# CortexM0_development_board.net
KiCad netlist of a schematic drawn in EAGLE
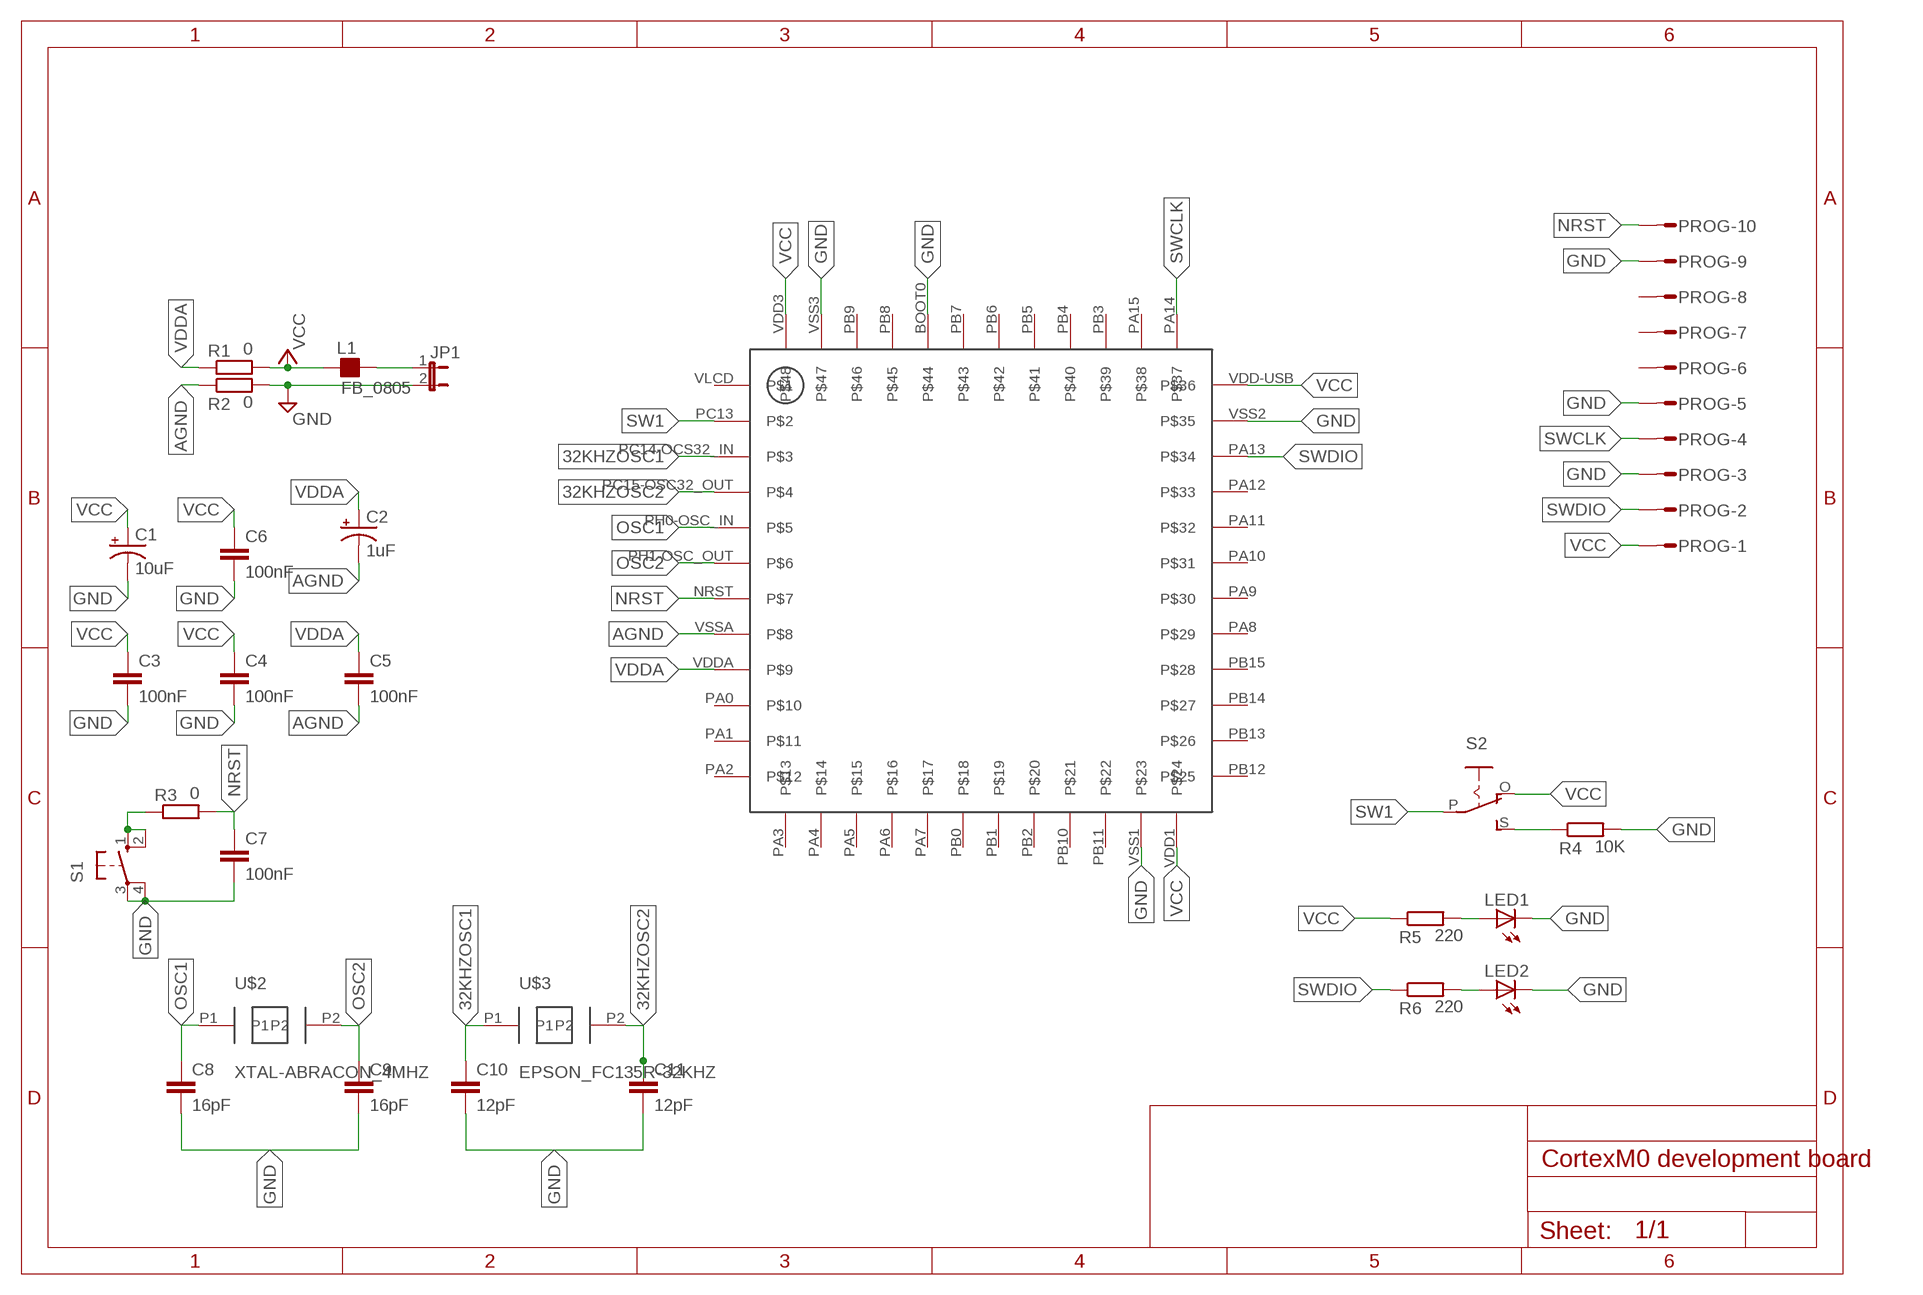
[diagram p0: schematic, sheet 1]

(export (version "E")
  (design (tool "Eeschema 10.0.6"))
  (components
    (comp (ref "C1")
      (value "10uF")
      (footprint "eagle-import:CAPMP3216X180N")
      (libsource (lib "eagle-import") (part "C-POL-USTANTALUM-1206(3216-METRIC)_"))
    )
    (comp (ref "C2")
      (value "1uF")
      (footprint "eagle-import:CAPMP3216X180N")
      (libsource (lib "eagle-import") (part "C-POL-USTANTALUM-1206(3216-METRIC)_"))
    )
    (comp (ref "C3")
      (value "100nF")
      (footprint "eagle-import:C0805")
      (libsource (lib "eagle-import") (part "C-EUC0805"))
    )
    (comp (ref "C4")
      (value "100nF")
      (footprint "eagle-import:C0805")
      (libsource (lib "eagle-import") (part "C-EUC0805"))
    )
    (comp (ref "C5")
      (value "100nF")
      (footprint "eagle-import:C0805")
      (libsource (lib "eagle-import") (part "C-EUC0805"))
    )
    (comp (ref "C6")
      (value "100nF")
      (footprint "eagle-import:C0805")
      (libsource (lib "eagle-import") (part "C-EUC0805"))
    )
    (comp (ref "C7")
      (value "100nF")
      (footprint "eagle-import:C0805")
      (libsource (lib "eagle-import") (part "C-EUC0805"))
    )
    (comp (ref "C8")
      (value "16pF")
      (footprint "eagle-import:C0805")
      (libsource (lib "eagle-import") (part "C-EUC0805"))
    )
    (comp (ref "C9")
      (value "16pF")
      (footprint "eagle-import:C0805")
      (libsource (lib "eagle-import") (part "C-EUC0805"))
    )
    (comp (ref "C10")
      (value "12pF")
      (footprint "eagle-import:C0805")
      (libsource (lib "eagle-import") (part "C-EUC0805"))
    )
    (comp (ref "C11")
      (value "12pF")
      (footprint "eagle-import:C0805")
      (libsource (lib "eagle-import") (part "C-EUC0805"))
    )
    (comp (ref "JP1")
      (value "JP1E")
      (footprint "eagle-import:JP1")
      (libsource (lib "eagle-import") (part "JP1E"))
    )
    (comp (ref "L1")
      (value "FB_0805")
      (footprint "eagle-import:L0805")
      (libsource (lib "eagle-import") (part "FB_0805"))
    )
    (comp (ref "LED1")
      (value "LED")
      (footprint "eagle-import:SMARTLED-TTW")
      (libsource (lib "eagle-import") (part "LED"))
    )
    (comp (ref "LED2")
      (value "LED")
      (footprint "eagle-import:SMARTLED-TTW")
      (libsource (lib "eagle-import") (part "LED"))
    )
    (comp (ref "PROG")
      (value "S10P")
      (footprint "eagle-import:S10P")
      (libsource (lib "eagle-import") (part "S10P"))
    )
    (comp (ref "R1")
      (value "0")
      (footprint "eagle-import:R0805")
      (libsource (lib "eagle-import") (part "R-EU_R0805"))
    )
    (comp (ref "R2")
      (value "0")
      (footprint "eagle-import:R0805")
      (libsource (lib "eagle-import") (part "R-EU_R0805"))
    )
    (comp (ref "R3")
      (value "0")
      (footprint "eagle-import:R0805")
      (libsource (lib "eagle-import") (part "R-EU_R0805"))
    )
    (comp (ref "R4")
      (value "10K")
      (footprint "eagle-import:R0805")
      (libsource (lib "eagle-import") (part "R-EU_R0805"))
    )
    (comp (ref "R5")
      (value "220")
      (footprint "eagle-import:R0805")
      (libsource (lib "eagle-import") (part "R-EU_R0805"))
    )
    (comp (ref "R6")
      (value "220")
      (footprint "eagle-import:R0805")
      (libsource (lib "eagle-import") (part "R-EU_R0805"))
    )
    (comp (ref "S1")
      (value "10-XX")
      (footprint "eagle-import:B3F-10XX")
      (fields (field (name "MPN") "B3F-1000"))
      (libsource (lib "eagle-import") (part "10-XX"))
    )
    (comp (ref "S2")
      (value "EG1218S")
      (footprint "eagle-import:EG1218")
      (libsource (lib "eagle-import") (part "EG1218S"))
    )
    (comp (ref "U$1")
      (value "LQFP_48")
      (footprint "eagle-import:STM32L083CZ")
      (libsource (lib "eagle-import") (part "LQFP_48"))
    )
    (comp (ref "U$2")
      (value "XTAL-ABRACON_4MHZ")
      (footprint "eagle-import:XTAL_ABRACON_4MHZ")
      (libsource (lib "eagle-import") (part "XTAL-ABRACON_4MHZ"))
    )
    (comp (ref "U$3")
      (value "EPSON_FC135R-32KHZ")
      (footprint "eagle-import:EPSON_FC135R_32KHZ")
      (libsource (lib "eagle-import") (part "EPSON_FC135R-32KHZ"))
    )
  )
  (nets
    (net (code "1") (name "32KHZOSC1") (class "Default")
      (node (ref "C10") (pin "1") (pinfunction "1_1") (pintype "passive"))
      (node (ref "U$1") (pin "PC14-OCS32_IN") (pinfunction "P$3_PC14-OCS32_IN") (pintype "bidirectional"))
      (node (ref "U$3") (pin "P1") (pinfunction "P1_P1") (pintype "bidirectional"))
    )
    (net (code "2") (name "32KHZOSC2") (class "Default")
      (node (ref "C11") (pin "1") (pinfunction "1_1") (pintype "passive"))
      (node (ref "U$1") (pin "PC15-OSC32_OUT") (pinfunction "P$4_PC15-OSC32_OUT") (pintype "bidirectional"))
      (node (ref "U$3") (pin "P2") (pinfunction "P2_P2") (pintype "bidirectional"))
    )
    (net (code "3") (name "AGND") (class "Default")
      (node (ref "C2") (pin "2") (pinfunction "-_2") (pintype "passive"))
      (node (ref "C5") (pin "2") (pinfunction "2_2") (pintype "passive"))
      (node (ref "R2") (pin "1") (pinfunction "1_1") (pintype "passive"))
      (node (ref "U$1") (pin "VSSA") (pinfunction "P$8_VSSA") (pintype "bidirectional"))
    )
    (net (code "4") (name "GND") (class "Default")
      (node (ref "C1") (pin "2") (pinfunction "-_2") (pintype "passive"))
      (node (ref "C10") (pin "2") (pinfunction "2_2") (pintype "passive"))
      (node (ref "C11") (pin "2") (pinfunction "2_2") (pintype "passive"))
      (node (ref "C3") (pin "2") (pinfunction "2_2") (pintype "passive"))
      (node (ref "C4") (pin "2") (pinfunction "2_2") (pintype "passive"))
      (node (ref "C6") (pin "2") (pinfunction "2_2") (pintype "passive"))
      (node (ref "C7") (pin "2") (pinfunction "2_2") (pintype "passive"))
      (node (ref "C8") (pin "2") (pinfunction "2_2") (pintype "passive"))
      (node (ref "C9") (pin "2") (pinfunction "2_2") (pintype "passive"))
      (node (ref "JP1") (pin "2") (pinfunction "2_2") (pintype "passive"))
      (node (ref "LED1") (pin "C@1") (pinfunction "C_C@1") (pintype "passive"))
      (node (ref "LED2") (pin "C@1") (pinfunction "C_C@1") (pintype "passive"))
      (node (ref "PROG") (pin "3") (pinfunction "S_3") (pintype "passive"))
      (node (ref "PROG") (pin "5") (pinfunction "S_5") (pintype "passive"))
      (node (ref "PROG") (pin "9") (pinfunction "S_9") (pintype "passive"))
      (node (ref "R2") (pin "2") (pinfunction "2_2") (pintype "passive"))
      (node (ref "R4") (pin "2") (pinfunction "2_2") (pintype "passive"))
      (node (ref "S1") (pin "3") (pinfunction "P_3") (pintype "passive"))
      (node (ref "S1") (pin "4") (pinfunction "P1_4") (pintype "passive"))
      (node (ref "U$1") (pin "BOOT0") (pinfunction "P$44_BOOT0") (pintype "bidirectional"))
      (node (ref "U$1") (pin "VSS1") (pinfunction "P$23_VSS1") (pintype "bidirectional"))
      (node (ref "U$1") (pin "VSS2") (pinfunction "P$35_VSS2") (pintype "bidirectional"))
      (node (ref "U$1") (pin "VSS3") (pinfunction "P$47_VSS3") (pintype "bidirectional"))
    )
    (net (code "5") (name "NRST") (class "Default")
      (node (ref "C7") (pin "1") (pinfunction "1_1") (pintype "passive"))
      (node (ref "PROG") (pin "10") (pinfunction "S_10") (pintype "passive"))
      (node (ref "R3") (pin "2") (pinfunction "2_2") (pintype "passive"))
      (node (ref "U$1") (pin "NRST") (pinfunction "P$7_NRST") (pintype "bidirectional"))
    )
    (net (code "6") (name "Net-(JP1-Pad1)") (class "Default")
      (node (ref "JP1") (pin "1") (pinfunction "1_1") (pintype "passive"))
      (node (ref "L1") (pin "2") (pinfunction "2_2") (pintype "passive"))
    )
    (net (code "7") (name "Net-(LED1-A)") (class "Default")
      (node (ref "LED1") (pin "A@1") (pinfunction "A_A@1") (pintype "passive"))
      (node (ref "R5") (pin "2") (pinfunction "2_2") (pintype "passive"))
    )
    (net (code "8") (name "Net-(LED2-A)") (class "Default")
      (node (ref "LED2") (pin "A@1") (pinfunction "A_A@1") (pintype "passive"))
      (node (ref "R6") (pin "2") (pinfunction "2_2") (pintype "passive"))
    )
    (net (code "9") (name "Net-(R4-Pad1)") (class "Default")
      (node (ref "R4") (pin "1") (pinfunction "1_1") (pintype "passive"))
      (node (ref "S2") (pin "S") (pinfunction "S_S") (pintype "passive"))
    )
    (net (code "10") (name "Net-(S1-S)") (class "Default")
      (node (ref "R3") (pin "1") (pinfunction "1_1") (pintype "passive"))
      (node (ref "S1") (pin "1") (pinfunction "S_1") (pintype "passive"))
      (node (ref "S1") (pin "2") (pinfunction "S1_2") (pintype "passive"))
    )
    (net (code "11") (name "OSC1") (class "Default")
      (node (ref "C8") (pin "1") (pinfunction "1_1") (pintype "passive"))
      (node (ref "U$1") (pin "PH0-OSC_IN") (pinfunction "P$5_PH0-OSC_IN") (pintype "bidirectional"))
      (node (ref "U$2") (pin "P1") (pinfunction "P1_P1") (pintype "bidirectional"))
    )
    (net (code "12") (name "OSC2") (class "Default")
      (node (ref "C9") (pin "1") (pinfunction "1_1") (pintype "passive"))
      (node (ref "U$1") (pin "PH1-OSC_OUT") (pinfunction "P$6_PH1-OSC_OUT") (pintype "bidirectional"))
      (node (ref "U$2") (pin "P2") (pinfunction "P2_P2") (pintype "bidirectional"))
    )
    (net (code "13") (name "SW1") (class "Default")
      (node (ref "S2") (pin "P") (pinfunction "P_P") (pintype "passive"))
      (node (ref "U$1") (pin "PC13") (pinfunction "P$2_PC13") (pintype "bidirectional"))
    )
    (net (code "14") (name "SWCLK") (class "Default")
      (node (ref "PROG") (pin "4") (pinfunction "S_4") (pintype "passive"))
      (node (ref "U$1") (pin "PA14") (pinfunction "P$37_PA14") (pintype "bidirectional"))
    )
    (net (code "15") (name "SWDIO") (class "Default")
      (node (ref "PROG") (pin "2") (pinfunction "S_2") (pintype "passive"))
      (node (ref "R6") (pin "1") (pinfunction "1_1") (pintype "passive"))
      (node (ref "U$1") (pin "PA13") (pinfunction "P$34_PA13") (pintype "bidirectional"))
    )
    (net (code "16") (name "VCC") (class "Default")
      (node (ref "C1") (pin "1") (pinfunction "+_1") (pintype "passive"))
      (node (ref "C3") (pin "1") (pinfunction "1_1") (pintype "passive"))
      (node (ref "C4") (pin "1") (pinfunction "1_1") (pintype "passive"))
      (node (ref "C6") (pin "1") (pinfunction "1_1") (pintype "passive"))
      (node (ref "L1") (pin "1") (pinfunction "1_1") (pintype "passive"))
      (node (ref "PROG") (pin "1") (pinfunction "S_1") (pintype "passive"))
      (node (ref "R1") (pin "2") (pinfunction "2_2") (pintype "passive"))
      (node (ref "R5") (pin "1") (pinfunction "1_1") (pintype "passive"))
      (node (ref "S2") (pin "O") (pinfunction "O_O") (pintype "passive"))
      (node (ref "U$1") (pin "VDD-USB") (pinfunction "P$36_VDD-USB") (pintype "bidirectional"))
      (node (ref "U$1") (pin "VDD1") (pinfunction "P$24_VDD1") (pintype "bidirectional"))
      (node (ref "U$1") (pin "VDD3") (pinfunction "P$48_VDD3") (pintype "bidirectional"))
    )
    (net (code "17") (name "VDDA") (class "Default")
      (node (ref "C2") (pin "1") (pinfunction "+_1") (pintype "passive"))
      (node (ref "C5") (pin "1") (pinfunction "1_1") (pintype "passive"))
      (node (ref "R1") (pin "1") (pinfunction "1_1") (pintype "passive"))
      (node (ref "U$1") (pin "VDDA") (pinfunction "P$9_VDDA") (pintype "bidirectional"))
    )
    (net (code "18") (name "unconnected-(PROGG-S-Pad6)") (class "Default")
      (node (ref "PROG") (pin "6") (pinfunction "S_6") (pintype "passive"))
    )
    (net (code "19") (name "unconnected-(PROGH-S-Pad7)") (class "Default")
      (node (ref "PROG") (pin "7") (pinfunction "S_7") (pintype "passive"))
    )
    (net (code "20") (name "unconnected-(PROGI-S-Pad8)") (class "Default")
      (node (ref "PROG") (pin "8") (pinfunction "S_8") (pintype "passive"))
    )
    (net (code "21") (name "unconnected-(U$1-P$1-PadVLCD)") (class "Default")
      (node (ref "U$1") (pin "VLCD") (pinfunction "P$1_VLCD") (pintype "bidirectional"))
    )
    (net (code "22") (name "unconnected-(U$1-P$10-PadPA0)") (class "Default")
      (node (ref "U$1") (pin "PA0") (pinfunction "P$10_PA0") (pintype "bidirectional"))
    )
    (net (code "23") (name "unconnected-(U$1-P$11-PadPA1)") (class "Default")
      (node (ref "U$1") (pin "PA1") (pinfunction "P$11_PA1") (pintype "bidirectional"))
    )
    (net (code "24") (name "unconnected-(U$1-P$12-PadPA2)") (class "Default")
      (node (ref "U$1") (pin "PA2") (pinfunction "P$12_PA2") (pintype "bidirectional"))
    )
    (net (code "25") (name "unconnected-(U$1-P$13-PadPA3)") (class "Default")
      (node (ref "U$1") (pin "PA3") (pinfunction "P$13_PA3") (pintype "bidirectional"))
    )
    (net (code "26") (name "unconnected-(U$1-P$14-PadPA4)") (class "Default")
      (node (ref "U$1") (pin "PA4") (pinfunction "P$14_PA4") (pintype "bidirectional"))
    )
    (net (code "27") (name "unconnected-(U$1-P$15-PadPA5)") (class "Default")
      (node (ref "U$1") (pin "PA5") (pinfunction "P$15_PA5") (pintype "bidirectional"))
    )
    (net (code "28") (name "unconnected-(U$1-P$16-PadPA6)") (class "Default")
      (node (ref "U$1") (pin "PA6") (pinfunction "P$16_PA6") (pintype "bidirectional"))
    )
    (net (code "29") (name "unconnected-(U$1-P$17-PadPA7)") (class "Default")
      (node (ref "U$1") (pin "PA7") (pinfunction "P$17_PA7") (pintype "bidirectional"))
    )
    (net (code "30") (name "unconnected-(U$1-P$18-PadPB0)") (class "Default")
      (node (ref "U$1") (pin "PB0") (pinfunction "P$18_PB0") (pintype "bidirectional"))
    )
    (net (code "31") (name "unconnected-(U$1-P$19-PadPB1)") (class "Default")
      (node (ref "U$1") (pin "PB1") (pinfunction "P$19_PB1") (pintype "bidirectional"))
    )
    (net (code "32") (name "unconnected-(U$1-P$20-PadPB2)") (class "Default")
      (node (ref "U$1") (pin "PB2") (pinfunction "P$20_PB2") (pintype "bidirectional"))
    )
    (net (code "33") (name "unconnected-(U$1-P$21-PadPB10)") (class "Default")
      (node (ref "U$1") (pin "PB10") (pinfunction "P$21_PB10") (pintype "bidirectional"))
    )
    (net (code "34") (name "unconnected-(U$1-P$22-PadPB11)") (class "Default")
      (node (ref "U$1") (pin "PB11") (pinfunction "P$22_PB11") (pintype "bidirectional"))
    )
    (net (code "35") (name "unconnected-(U$1-P$25-PadPB12)") (class "Default")
      (node (ref "U$1") (pin "PB12") (pinfunction "P$25_PB12") (pintype "bidirectional"))
    )
    (net (code "36") (name "unconnected-(U$1-P$26-PadPB13)") (class "Default")
      (node (ref "U$1") (pin "PB13") (pinfunction "P$26_PB13") (pintype "bidirectional"))
    )
    (net (code "37") (name "unconnected-(U$1-P$27-PadPB14)") (class "Default")
      (node (ref "U$1") (pin "PB14") (pinfunction "P$27_PB14") (pintype "bidirectional"))
    )
    (net (code "38") (name "unconnected-(U$1-P$28-PadPB15)") (class "Default")
      (node (ref "U$1") (pin "PB15") (pinfunction "P$28_PB15") (pintype "bidirectional"))
    )
    (net (code "39") (name "unconnected-(U$1-P$29-PadPA8)") (class "Default")
      (node (ref "U$1") (pin "PA8") (pinfunction "P$29_PA8") (pintype "bidirectional"))
    )
    (net (code "40") (name "unconnected-(U$1-P$30-PadPA9)") (class "Default")
      (node (ref "U$1") (pin "PA9") (pinfunction "P$30_PA9") (pintype "bidirectional"))
    )
    (net (code "41") (name "unconnected-(U$1-P$31-PadPA10)") (class "Default")
      (node (ref "U$1") (pin "PA10") (pinfunction "P$31_PA10") (pintype "bidirectional"))
    )
    (net (code "42") (name "unconnected-(U$1-P$32-PadPA11)") (class "Default")
      (node (ref "U$1") (pin "PA11") (pinfunction "P$32_PA11") (pintype "bidirectional"))
    )
    (net (code "43") (name "unconnected-(U$1-P$33-PadPA12)") (class "Default")
      (node (ref "U$1") (pin "PA12") (pinfunction "P$33_PA12") (pintype "bidirectional"))
    )
    (net (code "44") (name "unconnected-(U$1-P$38-PadPA15)") (class "Default")
      (node (ref "U$1") (pin "PA15") (pinfunction "P$38_PA15") (pintype "bidirectional"))
    )
    (net (code "45") (name "unconnected-(U$1-P$39-PadPB3)") (class "Default")
      (node (ref "U$1") (pin "PB3") (pinfunction "P$39_PB3") (pintype "bidirectional"))
    )
    (net (code "46") (name "unconnected-(U$1-P$40-PadPB4)") (class "Default")
      (node (ref "U$1") (pin "PB4") (pinfunction "P$40_PB4") (pintype "bidirectional"))
    )
    (net (code "47") (name "unconnected-(U$1-P$41-PadPB5)") (class "Default")
      (node (ref "U$1") (pin "PB5") (pinfunction "P$41_PB5") (pintype "bidirectional"))
    )
    (net (code "48") (name "unconnected-(U$1-P$42-PadPB6)") (class "Default")
      (node (ref "U$1") (pin "PB6") (pinfunction "P$42_PB6") (pintype "bidirectional"))
    )
    (net (code "49") (name "unconnected-(U$1-P$43-PadPB7)") (class "Default")
      (node (ref "U$1") (pin "PB7") (pinfunction "P$43_PB7") (pintype "bidirectional"))
    )
    (net (code "50") (name "unconnected-(U$1-P$45-PadPB8)") (class "Default")
      (node (ref "U$1") (pin "PB8") (pinfunction "P$45_PB8") (pintype "bidirectional"))
    )
    (net (code "51") (name "unconnected-(U$1-P$46-PadPB9)") (class "Default")
      (node (ref "U$1") (pin "PB9") (pinfunction "P$46_PB9") (pintype "bidirectional"))
    )
  )
)
